# PLD_RTC.net
KiCad netlist of a schematic drawn in Altium Designer
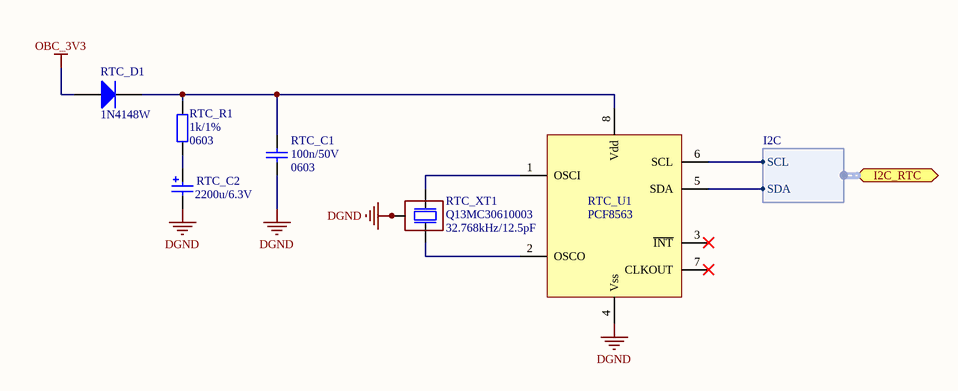
[diagram p0: PLD_RTC.SchDoc]

(export (version "E")
  (design (tool "Eeschema 10.0.6"))
  (components
    (comp (ref "RTC_C1")
      (value "100n/50V")
      (footprint "SMD_Capacitor_0603")
      (description "Ceramic Cap Kemet COTS 100n/50V X7R 0603")
      (fields
        (field (name "MANUFACTURER") "Kemet")
        (field (name "MANUFACTURERPARTNUMBER") "C0603T104K5RALTU")
        (field (name "PACKAGE") "0603")
      )
      (libsource (lib "capacitors") (part "Cer_C0603T104K5RALTU"))
    )
    (comp (ref "RTC_C2")
      (value "2200u/6.3V")
      (footprint "Tant_592D_X")
      (description "Vishay 592D Solid Tantalum Chip Capacitors.")
      (fields
        (field (name "MANUFACTURERPARTNUMBER") "592D228X96R3X2T20H")
        (field (name "MANUFACTURER") "Vishay")
      )
      (libsource (lib "capacitors") (part "Tant_592D228X96R3X2T20H"))
    )
    (comp (ref "RTC_D1")
      (value "1N4148W")
      (footprint "SOD-123")
      (description "Small Signal Fast Switching Diode")
      (fields (field (name "MANUFACTURER") "Vishay"))
      (libsource (lib "diodes") (part "1N4148W"))
    )
    (comp (ref "RTC_R1")
      (value "1k/1%")
      (footprint "SMD_Resistor_0603")
      (description "1k/1% Vishay CRCW 0603 Resistor. 100mW, 100ppm, 75V.")
      (fields
        (field (name "MANUFACTURER") "Vishay")
        (field (name "MANUFACTURERPARTNUMBER") "CRCW06031K00FKxxxx")
        (field (name "PACKAGE") "0603")
      )
      (libsource (lib "resistors") (part "CRCW06031K00FKxxxx"))
    )
    (comp (ref "RTC_U1")
      (value "~")
      (footprint "TSSOP8_L")
      (description "Real-time clock/calendar")
      (fields (field (name "MANUFACTURER") "NXP") (field (name "MANUFACTURERPARTNUMBER") "PCF8563"))
      (libsource (lib "microcircuits") (part "PCF8563"))
    )
    (comp (ref "RTC_XT1")
      (value "32.768kHz/12.5pF")
      (footprint "Epson_MC-306")
      (description "EPSON MC-306 32.768KHZ 12.5pF Crystal")
      (fields (field (name "MANUFACTURER") "Epson") (field (name "MANUFACTURERPARTNUMBER") "Q13MC30610003"))
      (libsource (lib "crystal") (part "Q13MC30610003"))
    )
  )
  (nets
    (net (code "2") (name "/SCL") (class "Default")
      (node (ref "RTC_U1") (pin "6") (pinfunction "SCL_6") (pintype "passive"))
    )
    (net (code "3") (name "/SDA") (class "Default")
      (node (ref "RTC_U1") (pin "5") (pinfunction "SDA_5") (pintype "passive"))
    )
    (net (code "5") (name "DGND") (class "Default")
      (node (ref "RTC_C1") (pin "2") (pinfunction "2_2") (pintype "passive"))
      (node (ref "RTC_C2") (pin "2") (pinfunction "2_2") (pintype "passive"))
      (node (ref "RTC_U1") (pin "4") (pinfunction "Vss_4") (pintype "passive"))
      (node (ref "RTC_XT1") (pin "2") (pinfunction "NC_2") (pintype "passive"))
      (node (ref "RTC_XT1") (pin "3") (pinfunction "NC_3") (pintype "passive"))
    )
    (net (code "6") (name "Net-(RTC_C2-Pad1)") (class "Default")
      (node (ref "RTC_C2") (pin "1") (pinfunction "1_1") (pintype "passive"))
      (node (ref "RTC_R1") (pin "2") (pinfunction "2_2") (pintype "passive"))
    )
    (net (code "7") (name "Net-(RTC_U1-OSCI)") (class "Default")
      (node (ref "RTC_U1") (pin "1") (pinfunction "OSCI_1") (pintype "passive"))
      (node (ref "RTC_XT1") (pin "1") (pinfunction "inp_1") (pintype "passive"))
    )
    (net (code "8") (name "Net-(RTC_U1-OSCO)") (class "Default")
      (node (ref "RTC_U1") (pin "2") (pinfunction "OSCO_2") (pintype "passive"))
      (node (ref "RTC_XT1") (pin "4") (pinfunction "out_4") (pintype "passive"))
    )
    (net (code "9") (name "Net-(RTC_U1-Vdd)") (class "Default")
      (node (ref "RTC_C1") (pin "1") (pinfunction "1_1") (pintype "passive"))
      (node (ref "RTC_D1") (pin "K") (pinfunction "K_K") (pintype "passive"))
      (node (ref "RTC_R1") (pin "1") (pinfunction "1_1") (pintype "passive"))
      (node (ref "RTC_U1") (pin "8") (pinfunction "Vdd_8") (pintype "passive"))
    )
    (net (code "10") (name "OBC_3V3") (class "Default")
      (node (ref "RTC_D1") (pin "A") (pinfunction "A_A") (pintype "passive"))
    )
    (net (code "11") (name "unconnected-(RTC_U1-CLKOUT-Pad7)") (class "Default")
      (node (ref "RTC_U1") (pin "7") (pinfunction "CLKOUT_7") (pintype "passive+no_connect"))
    )
    (net (code "12") (name "unconnected-(RTC_U1-~{INT}-Pad3)") (class "Default")
      (node (ref "RTC_U1") (pin "3") (pinfunction "~{INT}_3") (pintype "passive+no_connect"))
    )
  )
)
